# ArduinoInterface_v4.net
KiCad netlist of a schematic drawn in EAGLE
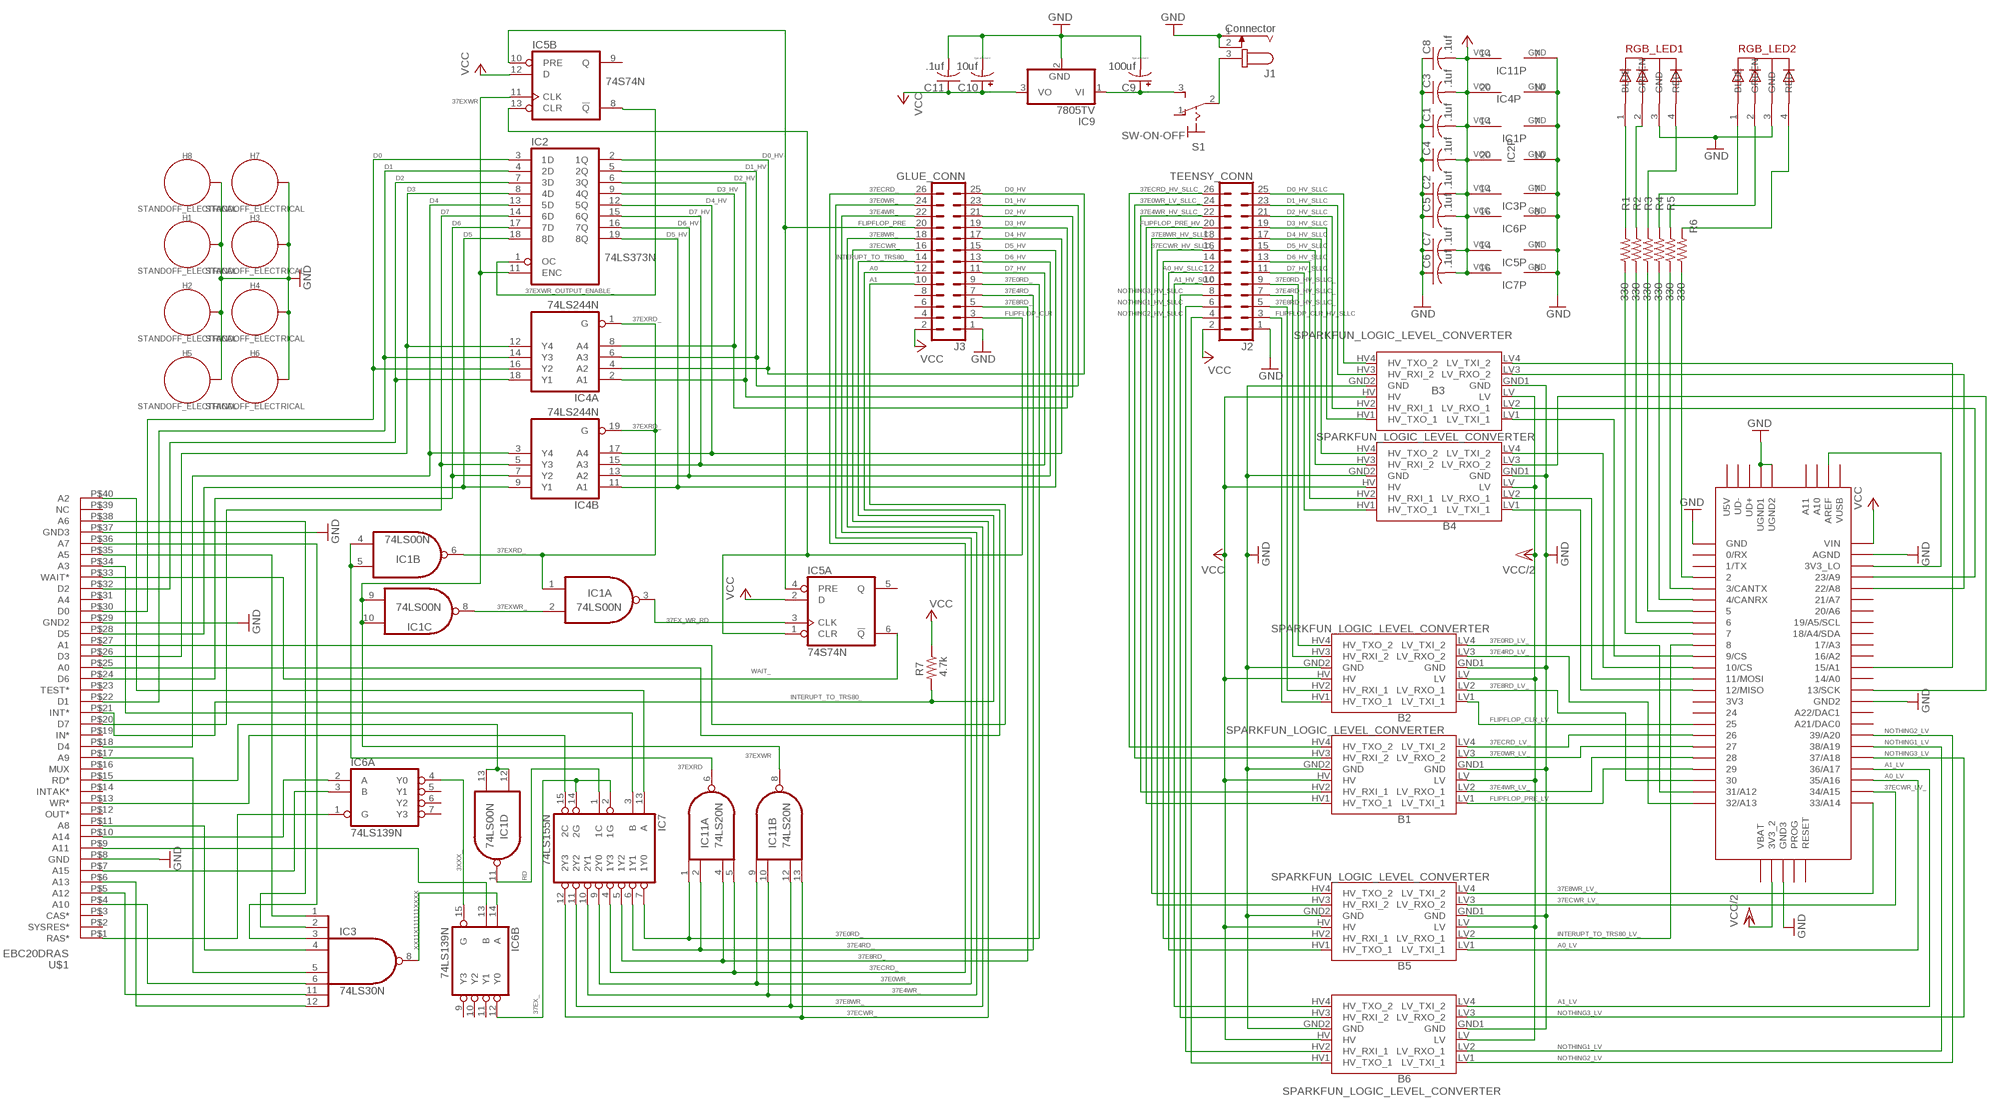
[diagram p0: schematic, sheet 1]

(export (version "E")
  (design (tool "Eeschema 10.0.6"))
  (components
    (comp (ref "B1")
      (value "SPARKFUN_LOGIC_LEVEL_CONVERTER")
      (footprint "eagle-import:SPARKFUN_LOGIC_LEVEL_CONVERTER")
      (libsource (lib "eagle-import") (part "SPARKFUN_LOGIC_LEVEL_CONVERTER"))
    )
    (comp (ref "B2")
      (value "SPARKFUN_LOGIC_LEVEL_CONVERTER")
      (footprint "eagle-import:SPARKFUN_LOGIC_LEVEL_CONVERTER")
      (libsource (lib "eagle-import") (part "SPARKFUN_LOGIC_LEVEL_CONVERTER"))
    )
    (comp (ref "B3")
      (value "SPARKFUN_LOGIC_LEVEL_CONVERTER")
      (footprint "eagle-import:SPARKFUN_LOGIC_LEVEL_CONVERTER")
      (libsource (lib "eagle-import") (part "SPARKFUN_LOGIC_LEVEL_CONVERTER"))
    )
    (comp (ref "B4")
      (value "SPARKFUN_LOGIC_LEVEL_CONVERTER")
      (footprint "eagle-import:SPARKFUN_LOGIC_LEVEL_CONVERTER")
      (libsource (lib "eagle-import") (part "SPARKFUN_LOGIC_LEVEL_CONVERTER"))
    )
    (comp (ref "B5")
      (value "SPARKFUN_LOGIC_LEVEL_CONVERTER")
      (footprint "eagle-import:SPARKFUN_LOGIC_LEVEL_CONVERTER")
      (libsource (lib "eagle-import") (part "SPARKFUN_LOGIC_LEVEL_CONVERTER"))
    )
    (comp (ref "B6")
      (value "SPARKFUN_LOGIC_LEVEL_CONVERTER")
      (footprint "eagle-import:SPARKFUN_LOGIC_LEVEL_CONVERTER")
      (libsource (lib "eagle-import") (part "SPARKFUN_LOGIC_LEVEL_CONVERTER"))
    )
    (comp (ref "C1")
      (value ".1uf")
      (footprint "eagle-import:C025-025X050")
      (libsource (lib "eagle-import") (part "C-US025-025X050"))
    )
    (comp (ref "C2")
      (value ".1uf")
      (footprint "eagle-import:C025-025X050")
      (libsource (lib "eagle-import") (part "C-US025-025X050"))
    )
    (comp (ref "C3")
      (value ".1uf")
      (footprint "eagle-import:C025-025X050")
      (libsource (lib "eagle-import") (part "C-US025-025X050"))
    )
    (comp (ref "C4")
      (value ".1uf")
      (footprint "eagle-import:C025-025X050")
      (libsource (lib "eagle-import") (part "C-US025-025X050"))
    )
    (comp (ref "C5")
      (value ".1uf")
      (footprint "eagle-import:C025-025X050")
      (libsource (lib "eagle-import") (part "C-US025-025X050"))
    )
    (comp (ref "C6")
      (value ".1uf")
      (footprint "eagle-import:C025-025X050")
      (libsource (lib "eagle-import") (part "C-US025-025X050"))
    )
    (comp (ref "C7")
      (value ".1uf")
      (footprint "eagle-import:C025-025X050")
      (libsource (lib "eagle-import") (part "C-US025-025X050"))
    )
    (comp (ref "C8")
      (value ".1uf")
      (footprint "eagle-import:C025-025X050")
      (libsource (lib "eagle-import") (part "C-US025-025X050"))
    )
    (comp (ref "C9")
      (value "100uf")
      (footprint "eagle-import:E5-6")
      (libsource (lib "eagle-import") (part "CPOL-USE5-6"))
    )
    (comp (ref "C10")
      (value "10uf")
      (footprint "eagle-import:E5-6")
      (libsource (lib "eagle-import") (part "CPOL-USE5-6"))
    )
    (comp (ref "C11")
      (value ".1uf")
      (footprint "eagle-import:C025-025X050")
      (libsource (lib "eagle-import") (part "C-US025-025X050"))
    )
    (comp (ref "H1")
      (value "STANDOFF_ELECTRICAL")
      (footprint "eagle-import:STANDOFF-ELECTRICAL")
      (libsource (lib "eagle-import") (part "STANDOFF_ELECTRICAL"))
    )
    (comp (ref "H2")
      (value "STANDOFF_ELECTRICAL")
      (footprint "eagle-import:STANDOFF-ELECTRICAL")
      (libsource (lib "eagle-import") (part "STANDOFF_ELECTRICAL"))
    )
    (comp (ref "H3")
      (value "STANDOFF_ELECTRICAL")
      (footprint "eagle-import:STANDOFF-ELECTRICAL")
      (libsource (lib "eagle-import") (part "STANDOFF_ELECTRICAL"))
    )
    (comp (ref "H4")
      (value "STANDOFF_ELECTRICAL")
      (footprint "eagle-import:STANDOFF-ELECTRICAL")
      (libsource (lib "eagle-import") (part "STANDOFF_ELECTRICAL"))
    )
    (comp (ref "H5")
      (value "STANDOFF_ELECTRICAL")
      (footprint "eagle-import:STANDOFF-ELECTRICAL")
      (libsource (lib "eagle-import") (part "STANDOFF_ELECTRICAL"))
    )
    (comp (ref "H6")
      (value "STANDOFF_ELECTRICAL")
      (footprint "eagle-import:STANDOFF-ELECTRICAL")
      (libsource (lib "eagle-import") (part "STANDOFF_ELECTRICAL"))
    )
    (comp (ref "H7")
      (value "STANDOFF_ELECTRICAL")
      (footprint "eagle-import:STANDOFF-ELECTRICAL")
      (libsource (lib "eagle-import") (part "STANDOFF_ELECTRICAL"))
    )
    (comp (ref "H8")
      (value "STANDOFF_ELECTRICAL")
      (footprint "eagle-import:STANDOFF-ELECTRICAL")
      (libsource (lib "eagle-import") (part "STANDOFF_ELECTRICAL"))
    )
    (comp (ref "IC1")
      (value "74LS00N")
      (footprint "eagle-import:DIL14")
      (libsource (lib "eagle-import") (part "7400NLS"))
    )
    (comp (ref "IC2")
      (value "74LS373N")
      (footprint "eagle-import:DIL20")
      (libsource (lib "eagle-import") (part "74373NLS"))
    )
    (comp (ref "IC3")
      (value "74LS30N")
      (footprint "eagle-import:DIL14")
      (libsource (lib "eagle-import") (part "7430NLS"))
    )
    (comp (ref "IC4")
      (value "74LS244N")
      (footprint "eagle-import:DIL20")
      (libsource (lib "eagle-import") (part "74244NLS"))
    )
    (comp (ref "IC5")
      (value "74S74N")
      (footprint "eagle-import:DIL14")
      (libsource (lib "eagle-import") (part "7474NS"))
    )
    (comp (ref "IC6")
      (value "74LS139N")
      (footprint "eagle-import:DIL16")
      (libsource (lib "eagle-import") (part "74139NLS"))
    )
    (comp (ref "IC7")
      (value "74LS155N")
      (footprint "eagle-import:DIL16")
      (libsource (lib "eagle-import") (part "74155NLS"))
    )
    (comp (ref "IC9")
      (value "7805TV")
      (footprint "eagle-import:TO220V")
      (libsource (lib "eagle-import") (part "78TV05"))
    )
    (comp (ref "IC11")
      (value "74LS20N")
      (footprint "eagle-import:DIL14")
      (libsource (lib "eagle-import") (part "7420NLS"))
    )
    (comp (ref "J1")
      (value "Connector")
      (footprint "eagle-import:SPC4077")
      (libsource (lib "eagle-import") (part "JACK-PLUG0"))
    )
    (comp (ref "J2")
      (value "TEENSY_CONN")
      (footprint "eagle-import:2X13")
      (libsource (lib "eagle-import") (part "CONN_13X22X13"))
    )
    (comp (ref "J3")
      (value "GLUE_CONN")
      (footprint "eagle-import:2X13")
      (libsource (lib "eagle-import") (part "CONN_13X22X13"))
    )
    (comp (ref "R1")
      (value "330")
      (footprint "eagle-import:0204V")
      (libsource (lib "eagle-import") (part "R-US_0204/2V"))
    )
    (comp (ref "R2")
      (value "330")
      (footprint "eagle-import:0204V")
      (libsource (lib "eagle-import") (part "R-US_0204/2V"))
    )
    (comp (ref "R3")
      (value "330")
      (footprint "eagle-import:0204V")
      (libsource (lib "eagle-import") (part "R-US_0204/2V"))
    )
    (comp (ref "R4")
      (value "330")
      (footprint "eagle-import:0204V")
      (libsource (lib "eagle-import") (part "R-US_0204/2V"))
    )
    (comp (ref "R5")
      (value "330")
      (footprint "eagle-import:0204V")
      (libsource (lib "eagle-import") (part "R-US_0204/2V"))
    )
    (comp (ref "R6")
      (value "330")
      (footprint "eagle-import:0204V")
      (libsource (lib "eagle-import") (part "R-US_0204/2V"))
    )
    (comp (ref "R7")
      (value "4.7k")
      (footprint "eagle-import:0204V")
      (libsource (lib "eagle-import") (part "R-US_0204/2V"))
    )
    (comp (ref "RGB_LED1")
      (value "5MMRGBLED")
      (footprint "eagle-import:LED5MMRGB")
      (libsource (lib "eagle-import") (part "5MMRGBLED"))
    )
    (comp (ref "RGB_LED2")
      (value "5MMRGBLED")
      (footprint "eagle-import:LED5MMRGB")
      (libsource (lib "eagle-import") (part "5MMRGBLED"))
    )
    (comp (ref "S1")
      (value "SW-ON-OFF")
      (footprint "eagle-import:M9040P")
      (libsource (lib "eagle-import") (part "M9040P"))
    )
    (comp (ref "U$1")
      (value "EBC20DRAS")
      (footprint "eagle-import:EBC20DRAS")
      (libsource (lib "eagle-import") (part "EBC20DRAS"))
    )
    (comp (ref "U$2")
      (value "TEENSY_3.5/3.6")
      (footprint "eagle-import:TEENSY_3.5_3.6")
      (libsource (lib "eagle-import") (part "TEENSY_3.5/3.6"))
    )
  )
  (nets
    (net (code "1") (name "/3XXX_") (class "Default")
      (node (ref "IC6") (pin "15") (pinfunction "G_15") (pintype "input"))
      (node (ref "IC6") (pin "4") (pinfunction "Y0_4") (pintype "output"))
    )
    (net (code "2") (name "/37E0RD_") (class "Default")
      (node (ref "IC11") (pin "1") (pinfunction "I0_1") (pintype "input"))
      (node (ref "IC7") (pin "7") (pinfunction "1Y0_7") (pintype "output"))
      (node (ref "J3") (pin "9") (pinfunction "9_9") (pintype "passive"))
    )
    (net (code "3") (name "/37E0RD_HV_SLLC_") (class "Default")
      (node (ref "B2") (pin "HV4") (pinfunction "HV_TXO_2_HV4") (pintype "bidirectional"))
      (node (ref "J2") (pin "9") (pinfunction "9_9") (pintype "passive"))
    )
    (net (code "4") (name "/37E0RD_LV_") (class "Default")
      (node (ref "B2") (pin "LV4") (pinfunction "LV_TXI_2_LV4") (pintype "bidirectional"))
      (node (ref "U$2") (pin "31/A12") (pinfunction "31/A12_31/A12") (pintype "bidirectional"))
    )
    (net (code "5") (name "/37E0WR_") (class "Default")
      (node (ref "IC11") (pin "9") (pinfunction "I0_9") (pintype "input"))
      (node (ref "IC7") (pin "9") (pinfunction "2Y0_9") (pintype "output"))
      (node (ref "J3") (pin "24") (pinfunction "24_24") (pintype "passive"))
    )
    (net (code "6") (name "/37E0WR_LV_") (class "Default")
      (node (ref "B1") (pin "LV3") (pinfunction "LV_RXO_2_LV3") (pintype "bidirectional"))
      (node (ref "U$2") (pin "27") (pinfunction "27_27") (pintype "bidirectional"))
    )
    (net (code "7") (name "/37E0WR_LV_SLLC_") (class "Default")
      (node (ref "B1") (pin "HV3") (pinfunction "HV_RXI_2_HV3") (pintype "bidirectional"))
      (node (ref "J2") (pin "24") (pinfunction "24_24") (pintype "passive"))
    )
    (net (code "8") (name "/37E4RD_") (class "Default")
      (node (ref "IC11") (pin "2") (pinfunction "I1_2") (pintype "input"))
      (node (ref "IC7") (pin "6") (pinfunction "1Y1_6") (pintype "output"))
      (node (ref "J3") (pin "7") (pinfunction "7_7") (pintype "passive"))
    )
    (net (code "9") (name "/37E4RD_HV_SLLC_") (class "Default")
      (node (ref "B2") (pin "HV3") (pinfunction "HV_RXI_2_HV3") (pintype "bidirectional"))
      (node (ref "J2") (pin "7") (pinfunction "7_7") (pintype "passive"))
    )
    (net (code "10") (name "/37E4RD_LV_") (class "Default")
      (node (ref "B2") (pin "LV3") (pinfunction "LV_RXO_2_LV3") (pintype "bidirectional"))
      (node (ref "U$2") (pin "32/A13") (pinfunction "32/A13_32/A13") (pintype "bidirectional"))
    )
    (net (code "11") (name "/37E4WR_") (class "Default")
      (node (ref "IC11") (pin "10") (pinfunction "I1_10") (pintype "input"))
      (node (ref "IC7") (pin "10") (pinfunction "2Y1_10") (pintype "output"))
      (node (ref "J3") (pin "22") (pinfunction "22_22") (pintype "passive"))
    )
    (net (code "12") (name "/37E4WR_HV_SLLC_") (class "Default")
      (node (ref "B1") (pin "HV2") (pinfunction "HV_RXI_1_HV2") (pintype "bidirectional"))
      (node (ref "J2") (pin "22") (pinfunction "22_22") (pintype "passive"))
    )
    (net (code "13") (name "/37E4WR_LV_") (class "Default")
      (node (ref "B1") (pin "LV2") (pinfunction "LV_RXO_1_LV2") (pintype "bidirectional"))
      (node (ref "U$2") (pin "28") (pinfunction "28_28") (pintype "bidirectional"))
    )
    (net (code "14") (name "/37E8RD_") (class "Default")
      (node (ref "IC11") (pin "4") (pinfunction "I2_4") (pintype "input"))
      (node (ref "IC7") (pin "5") (pinfunction "1Y2_5") (pintype "output"))
      (node (ref "J3") (pin "5") (pinfunction "5_5") (pintype "passive"))
    )
    (net (code "15") (name "/37E8RD_HV_SLLC_") (class "Default")
      (node (ref "B2") (pin "HV2") (pinfunction "HV_RXI_1_HV2") (pintype "bidirectional"))
      (node (ref "J2") (pin "5") (pinfunction "5_5") (pintype "passive"))
    )
    (net (code "16") (name "/37E8RD_LV_") (class "Default")
      (node (ref "B2") (pin "LV2") (pinfunction "LV_RXO_1_LV2") (pintype "bidirectional"))
      (node (ref "U$2") (pin "30") (pinfunction "30_30") (pintype "bidirectional"))
    )
    (net (code "17") (name "/37E8WR_") (class "Default")
      (node (ref "IC11") (pin "12") (pinfunction "I2_12") (pintype "input"))
      (node (ref "IC7") (pin "11") (pinfunction "2Y2_11") (pintype "output"))
      (node (ref "J3") (pin "18") (pinfunction "18_18") (pintype "passive"))
    )
    (net (code "18") (name "/37E8WR_HV_SLLC_") (class "Default")
      (node (ref "B5") (pin "HV4") (pinfunction "HV_TXO_2_HV4") (pintype "bidirectional"))
      (node (ref "J2") (pin "18") (pinfunction "18_18") (pintype "passive"))
    )
    (net (code "19") (name "/37E8WR_LV_") (class "Default")
      (node (ref "B5") (pin "LV4") (pinfunction "LV_TXI_2_LV4") (pintype "bidirectional"))
      (node (ref "U$2") (pin "33/A14") (pinfunction "33/A14_33/A14") (pintype "bidirectional"))
    )
    (net (code "20") (name "/37ECRD_") (class "Default")
      (node (ref "IC11") (pin "5") (pinfunction "I3_5") (pintype "input"))
      (node (ref "IC7") (pin "4") (pinfunction "1Y3_4") (pintype "output"))
      (node (ref "J3") (pin "26") (pinfunction "26_26") (pintype "passive"))
    )
    (net (code "21") (name "/37ECRD_HV_SLLC_") (class "Default")
      (node (ref "B1") (pin "HV4") (pinfunction "HV_TXO_2_HV4") (pintype "bidirectional"))
      (node (ref "J2") (pin "26") (pinfunction "26_26") (pintype "passive"))
    )
    (net (code "22") (name "/37ECRD_LV_") (class "Default")
      (node (ref "B1") (pin "LV4") (pinfunction "LV_TXI_2_LV4") (pintype "bidirectional"))
      (node (ref "U$2") (pin "26") (pinfunction "26_26") (pintype "bidirectional"))
    )
    (net (code "23") (name "/37ECWR_") (class "Default")
      (node (ref "IC11") (pin "13") (pinfunction "I3_13") (pintype "input"))
      (node (ref "IC7") (pin "12") (pinfunction "2Y3_12") (pintype "output"))
      (node (ref "J3") (pin "16") (pinfunction "16_16") (pintype "passive"))
    )
    (net (code "24") (name "/37ECWR_HV_SLLC_") (class "Default")
      (node (ref "B5") (pin "HV3") (pinfunction "HV_RXI_2_HV3") (pintype "bidirectional"))
      (node (ref "J2") (pin "16") (pinfunction "16_16") (pintype "passive"))
    )
    (net (code "25") (name "/37ECWR_LV_") (class "Default")
      (node (ref "B5") (pin "LV3") (pinfunction "LV_RXO_2_LV3") (pintype "bidirectional"))
      (node (ref "U$2") (pin "34/A15") (pinfunction "34/A15_34/A15") (pintype "bidirectional"))
    )
    (net (code "26") (name "/37EXRD") (class "Default")
      (node (ref "IC1") (pin "4") (pinfunction "I0_4") (pintype "input"))
      (node (ref "IC1") (pin "5") (pinfunction "I1_5") (pintype "input"))
      (node (ref "IC11") (pin "6") (pinfunction "O_6") (pintype "output"))
    )
    (net (code "27") (name "/37EXRD_") (class "Default")
      (node (ref "IC1") (pin "1") (pinfunction "I0_1") (pintype "input"))
      (node (ref "IC1") (pin "6") (pinfunction "O_6") (pintype "output"))
      (node (ref "IC4") (pin "1") (pinfunction "G_1") (pintype "input"))
      (node (ref "IC4") (pin "19") (pinfunction "G_19") (pintype "input"))
    )
    (net (code "28") (name "/37EXWR") (class "Default")
      (node (ref "IC1") (pin "10") (pinfunction "I1_10") (pintype "input"))
      (node (ref "IC1") (pin "9") (pinfunction "I0_9") (pintype "input"))
      (node (ref "IC11") (pin "8") (pinfunction "O_8") (pintype "output"))
      (node (ref "IC2") (pin "11") (pinfunction "ENC_11") (pintype "input"))
      (node (ref "IC5") (pin "11") (pinfunction "CLK_11") (pintype "input"))
    )
    (net (code "29") (name "/37EXWR_") (class "Default")
      (node (ref "IC1") (pin "2") (pinfunction "I1_2") (pintype "input"))
      (node (ref "IC1") (pin "8") (pinfunction "O_8") (pintype "output"))
    )
    (net (code "30") (name "/37EXWR_OUTPUT_ENABLE_") (class "Default")
      (node (ref "IC2") (pin "1") (pinfunction "OC_1") (pintype "input"))
      (node (ref "IC5") (pin "8") (pinfunction "~{Q}_8") (pintype "output"))
    )
    (net (code "31") (name "/37EX_") (class "Default")
      (node (ref "IC6") (pin "12") (pinfunction "Y0_12") (pintype "output"))
      (node (ref "IC7") (pin "14") (pinfunction "2G_14") (pintype "input"))
      (node (ref "IC7") (pin "2") (pinfunction "1G_2") (pintype "input"))
    )
    (net (code "32") (name "/37EX_WR_RD") (class "Default")
      (node (ref "IC1") (pin "3") (pinfunction "O_3") (pintype "output"))
      (node (ref "IC5") (pin "3") (pinfunction "CLK_3") (pintype "input"))
    )
    (net (code "33") (name "/A0") (class "Default")
      (node (ref "J3") (pin "12") (pinfunction "12_12") (pintype "passive"))
      (node (ref "U$1") (pin "P$25") (pinfunction "A0_P$25") (pintype "bidirectional"))
    )
    (net (code "34") (name "/A0_HV_SLLC") (class "Default")
      (node (ref "B5") (pin "HV1") (pinfunction "HV_TXO_1_HV1") (pintype "bidirectional"))
      (node (ref "J2") (pin "12") (pinfunction "12_12") (pintype "passive"))
    )
    (net (code "35") (name "/A0_LV") (class "Default")
      (node (ref "B5") (pin "LV1") (pinfunction "LV_TXI_1_LV1") (pintype "bidirectional"))
      (node (ref "U$2") (pin "35/A16") (pinfunction "35/A16_35/A16") (pintype "bidirectional"))
    )
    (net (code "36") (name "/A1") (class "Default")
      (node (ref "J3") (pin "10") (pinfunction "10_10") (pintype "passive"))
      (node (ref "U$1") (pin "P$27") (pinfunction "A1_P$27") (pintype "bidirectional"))
    )
    (net (code "37") (name "/A1_HV_SLLC") (class "Default")
      (node (ref "B6") (pin "HV4") (pinfunction "HV_TXO_2_HV4") (pintype "bidirectional"))
      (node (ref "J2") (pin "10") (pinfunction "10_10") (pintype "passive"))
    )
    (net (code "38") (name "/A1_LV") (class "Default")
      (node (ref "B6") (pin "LV4") (pinfunction "LV_TXI_2_LV4") (pintype "bidirectional"))
      (node (ref "U$2") (pin "36/A17") (pinfunction "36/A17_36/A17") (pintype "bidirectional"))
    )
    (net (code "39") (name "/D0") (class "Default")
      (node (ref "IC2") (pin "3") (pinfunction "1D_3") (pintype "input"))
      (node (ref "IC4") (pin "16") (pinfunction "Y2_16") (pintype "tri_state"))
      (node (ref "U$1") (pin "P$30") (pinfunction "D0_P$30") (pintype "bidirectional"))
    )
    (net (code "40") (name "/D0_HV") (class "Default")
      (node (ref "IC2") (pin "2") (pinfunction "1Q_2") (pintype "tri_state"))
      (node (ref "IC4") (pin "4") (pinfunction "A2_4") (pintype "input"))
      (node (ref "J3") (pin "25") (pinfunction "25_25") (pintype "passive"))
    )
    (net (code "41") (name "/D0_HV_SLLC") (class "Default")
      (node (ref "B3") (pin "HV4") (pinfunction "HV_TXO_2_HV4") (pintype "bidirectional"))
      (node (ref "J2") (pin "25") (pinfunction "25_25") (pintype "passive"))
    )
    (net (code "42") (name "/D1") (class "Default")
      (node (ref "IC2") (pin "4") (pinfunction "2D_4") (pintype "input"))
      (node (ref "IC4") (pin "14") (pinfunction "Y3_14") (pintype "tri_state"))
      (node (ref "U$1") (pin "P$22") (pinfunction "D1_P$22") (pintype "bidirectional"))
    )
    (net (code "43") (name "/D1_HV") (class "Default")
      (node (ref "IC2") (pin "5") (pinfunction "2Q_5") (pintype "tri_state"))
      (node (ref "IC4") (pin "6") (pinfunction "A3_6") (pintype "input"))
      (node (ref "J3") (pin "23") (pinfunction "23_23") (pintype "passive"))
    )
    (net (code "44") (name "/D1_HV_SLLC") (class "Default")
      (node (ref "B3") (pin "HV3") (pinfunction "HV_RXI_2_HV3") (pintype "bidirectional"))
      (node (ref "J2") (pin "23") (pinfunction "23_23") (pintype "passive"))
    )
    (net (code "45") (name "/D2") (class "Default")
      (node (ref "IC2") (pin "7") (pinfunction "3D_7") (pintype "input"))
      (node (ref "IC4") (pin "18") (pinfunction "Y1_18") (pintype "tri_state"))
      (node (ref "U$1") (pin "P$32") (pinfunction "D2_P$32") (pintype "bidirectional"))
    )
    (net (code "46") (name "/D2_HV") (class "Default")
      (node (ref "IC2") (pin "6") (pinfunction "3Q_6") (pintype "tri_state"))
      (node (ref "IC4") (pin "2") (pinfunction "A1_2") (pintype "input"))
      (node (ref "J3") (pin "21") (pinfunction "21_21") (pintype "passive"))
    )
    (net (code "47") (name "/D2_HV_SLLC") (class "Default")
      (node (ref "B3") (pin "HV2") (pinfunction "HV_RXI_1_HV2") (pintype "bidirectional"))
      (node (ref "J2") (pin "21") (pinfunction "21_21") (pintype "passive"))
    )
    (net (code "48") (name "/D3") (class "Default")
      (node (ref "IC2") (pin "8") (pinfunction "4D_8") (pintype "input"))
      (node (ref "IC4") (pin "12") (pinfunction "Y4_12") (pintype "tri_state"))
      (node (ref "U$1") (pin "P$26") (pinfunction "D3_P$26") (pintype "bidirectional"))
    )
    (net (code "49") (name "/D3_HV") (class "Default")
      (node (ref "IC2") (pin "9") (pinfunction "4Q_9") (pintype "tri_state"))
      (node (ref "IC4") (pin "8") (pinfunction "A4_8") (pintype "input"))
      (node (ref "J3") (pin "19") (pinfunction "19_19") (pintype "passive"))
    )
    (net (code "50") (name "/D3_HV_SLLC") (class "Default")
      (node (ref "B3") (pin "HV1") (pinfunction "HV_TXO_1_HV1") (pintype "bidirectional"))
      (node (ref "J2") (pin "19") (pinfunction "19_19") (pintype "passive"))
    )
    (net (code "51") (name "/D4") (class "Default")
      (node (ref "IC2") (pin "13") (pinfunction "5D_13") (pintype "input"))
      (node (ref "IC4") (pin "3") (pinfunction "Y4_3") (pintype "tri_state"))
      (node (ref "U$1") (pin "P$18") (pinfunction "D4_P$18") (pintype "bidirectional"))
    )
    (net (code "52") (name "/D4_HV") (class "Default")
      (node (ref "IC2") (pin "12") (pinfunction "5Q_12") (pintype "tri_state"))
      (node (ref "IC4") (pin "17") (pinfunction "A4_17") (pintype "input"))
      (node (ref "J3") (pin "17") (pinfunction "17_17") (pintype "passive"))
    )
    (net (code "53") (name "/D4_HV_SLLC") (class "Default")
      (node (ref "B4") (pin "HV4") (pinfunction "HV_TXO_2_HV4") (pintype "bidirectional"))
      (node (ref "J2") (pin "17") (pinfunction "17_17") (pintype "passive"))
    )
    (net (code "54") (name "/D5") (class "Default")
      (node (ref "IC2") (pin "18") (pinfunction "8D_18") (pintype "input"))
      (node (ref "IC4") (pin "9") (pinfunction "Y1_9") (pintype "tri_state"))
      (node (ref "U$1") (pin "P$28") (pinfunction "D5_P$28") (pintype "bidirectional"))
    )
    (net (code "55") (name "/D5_HV") (class "Default")
      (node (ref "IC2") (pin "19") (pinfunction "8Q_19") (pintype "tri_state"))
      (node (ref "IC4") (pin "11") (pinfunction "A1_11") (pintype "input"))
      (node (ref "J3") (pin "15") (pinfunction "15_15") (pintype "passive"))
    )
    (net (code "56") (name "/D5_HV_SLLC") (class "Default")
      (node (ref "B4") (pin "HV3") (pinfunction "HV_RXI_2_HV3") (pintype "bidirectional"))
      (node (ref "J2") (pin "15") (pinfunction "15_15") (pintype "passive"))
    )
    (net (code "57") (name "/D6") (class "Default")
      (node (ref "IC2") (pin "17") (pinfunction "7D_17") (pintype "input"))
      (node (ref "IC4") (pin "7") (pinfunction "Y2_7") (pintype "tri_state"))
      (node (ref "U$1") (pin "P$24") (pinfunction "D6_P$24") (pintype "bidirectional"))
    )
    (net (code "58") (name "/D6_HV") (class "Default")
      (node (ref "IC2") (pin "16") (pinfunction "7Q_16") (pintype "tri_state"))
      (node (ref "IC4") (pin "13") (pinfunction "A2_13") (pintype "input"))
      (node (ref "J3") (pin "13") (pinfunction "13_13") (pintype "passive"))
    )
    (net (code "59") (name "/D6_HV_SLLC") (class "Default")
      (node (ref "B4") (pin "HV2") (pinfunction "HV_RXI_1_HV2") (pintype "bidirectional"))
      (node (ref "J2") (pin "13") (pinfunction "13_13") (pintype "passive"))
    )
    (net (code "60") (name "/D7") (class "Default")
      (node (ref "IC2") (pin "14") (pinfunction "6D_14") (pintype "input"))
      (node (ref "IC4") (pin "5") (pinfunction "Y3_5") (pintype "tri_state"))
      (node (ref "U$1") (pin "P$20") (pinfunction "D7_P$20") (pintype "bidirectional"))
    )
    (net (code "61") (name "/D7_HV") (class "Default")
      (node (ref "IC2") (pin "15") (pinfunction "6Q_15") (pintype "tri_state"))
      (node (ref "IC4") (pin "15") (pinfunction "A3_15") (pintype "input"))
      (node (ref "J3") (pin "11") (pinfunction "11_11") (pintype "passive"))
    )
    (net (code "62") (name "/D7_HV_SLLC") (class "Default")
      (node (ref "B4") (pin "HV1") (pinfunction "HV_TXO_1_HV1") (pintype "bidirectional"))
      (node (ref "J2") (pin "11") (pinfunction "11_11") (pintype "passive"))
    )
    (net (code "63") (name "/FLIPFLOP_CLR") (class "Default")
      (node (ref "IC5") (pin "1") (pinfunction "CLR_1") (pintype "input"))
      (node (ref "IC5") (pin "13") (pinfunction "CLR_13") (pintype "input"))
      (node (ref "J3") (pin "3") (pinfunction "3_3") (pintype "passive"))
    )
    (net (code "64") (name "/FLIPFLOP_CLR_HV_SLLC") (class "Default")
      (node (ref "B2") (pin "HV1") (pinfunction "HV_TXO_1_HV1") (pintype "bidirectional"))
      (node (ref "J2") (pin "3") (pinfunction "3_3") (pintype "passive"))
    )
    (net (code "65") (name "/FLIPFLOP_CLR_LV") (class "Default")
      (node (ref "B2") (pin "LV1") (pinfunction "LV_TXI_1_LV1") (pintype "bidirectional"))
      (node (ref "U$2") (pin "25") (pinfunction "25_25") (pintype "bidirectional"))
    )
    (net (code "66") (name "/FLIPFLOP_PRE") (class "Default")
      (node (ref "IC5") (pin "10") (pinfunction "PRE_10") (pintype "input"))
      (node (ref "IC5") (pin "4") (pinfunction "PRE_4") (pintype "input"))
      (node (ref "J3") (pin "20") (pinfunction "20_20") (pintype "passive"))
    )
    (net (code "67") (name "/FLIPFLOP_PRE_HV") (class "Default")
      (node (ref "B1") (pin "HV1") (pinfunction "HV_TXO_1_HV1") (pintype "bidirectional"))
      (node (ref "J2") (pin "20") (pinfunction "20_20") (pintype "passive"))
    )
    (net (code "68") (name "/FLIPFLOP_PRE_LV") (class "Default")
      (node (ref "B1") (pin "LV1") (pinfunction "LV_TXI_1_LV1") (pintype "bidirectional"))
      (node (ref "U$2") (pin "29") (pinfunction "29_29") (pintype "bidirectional"))
    )
    (net (code "69") (name "/INTERUPT_TO_TRS80_") (class "Default")
      (node (ref "J3") (pin "14") (pinfunction "14_14") (pintype "passive"))
      (node (ref "R7") (pin "2") (pinfunction "2_2") (pintype "passive"))
      (node (ref "U$1") (pin "P$21") (pinfunction "INT*_P$21") (pintype "bidirectional"))
    )
    (net (code "70") (name "/INTERUPT_TO_TRS80_LV_") (class "Default")
      (node (ref "B5") (pin "LV2") (pinfunction "LV_RXO_1_LV2") (pintype "bidirectional"))
      (node (ref "U$2") (pin "8") (pinfunction "8_8") (pintype "bidirectional"))
    )
    (net (code "71") (name "/NOTHING1_HV_SLLC") (class "Default")
      (node (ref "B6") (pin "HV2") (pinfunction "HV_RXI_1_HV2") (pintype "bidirectional"))
      (node (ref "J2") (pin "6") (pinfunction "6_6") (pintype "passive"))
    )
    (net (code "72") (name "/NOTHING1_LV") (class "Default")
      (node (ref "B6") (pin "LV2") (pinfunction "LV_RXO_1_LV2") (pintype "bidirectional"))
      (node (ref "U$2") (pin "38/A19") (pinfunction "38/A19_38/A19") (pintype "bidirectional"))
    )
    (net (code "73") (name "/NOTHING2_HV_SLLC") (class "Default")
      (node (ref "B6") (pin "HV1") (pinfunction "HV_TXO_1_HV1") (pintype "bidirectional"))
      (node (ref "J2") (pin "4") (pinfunction "4_4") (pintype "passive"))
    )
    (net (code "74") (name "/NOTHING2_LV") (class "Default")
      (node (ref "B6") (pin "LV1") (pinfunction "LV_TXI_1_LV1") (pintype "bidirectional"))
      (node (ref "U$2") (pin "39/A20") (pinfunction "39/A20_39/A20") (pintype "bidirectional"))
    )
    (net (code "75") (name "/NOTHING3_HV_SLLC") (class "Default")
      (node (ref "B6") (pin "HV3") (pinfunction "HV_RXI_2_HV3") (pintype "bidirectional"))
      (node (ref "J2") (pin "8") (pinfunction "8_8") (pintype "passive"))
    )
    (net (code "76") (name "/NOTHING3_LV") (class "Default")
      (node (ref "B6") (pin "LV3") (pinfunction "LV_RXO_2_LV3") (pintype "bidirectional"))
      (node (ref "U$2") (pin "37/A18") (pinfunction "37/A18_37/A18") (pintype "bidirectional"))
    )
    (net (code "77") (name "/RD") (class "Default")
      (node (ref "IC1") (pin "11") (pinfunction "O_11") (pintype "output"))
      (node (ref "IC7") (pin "1") (pinfunction "1C_1") (pintype "input"))
    )
    (net (code "78") (name "/WAIT_") (class "Default")
      (node (ref "IC5") (pin "6") (pinfunction "~{Q}_6") (pintype "output"))
      (node (ref "U$1") (pin "P$33") (pinfunction "WAIT*_P$33") (pintype "bidirectional"))
    )
    (net (code "79") (name "/XX11X111111XXXX") (class "Default")
      (node (ref "IC3") (pin "8") (pinfunction "O_8") (pintype "output"))
      (node (ref "IC6") (pin "14") (pinfunction "A_14") (pintype "input"))
    )
    (net (code "80") (name "GND") (class "Default")
      (node (ref "B1") (pin "GND1") (pinfunction "GND_GND1") (pintype "power_in"))
      (node (ref "B1") (pin "GND2") (pinfunction "GND_GND2") (pintype "power_in"))
      (node (ref "B2") (pin "GND1") (pinfunction "GND_GND1") (pintype "power_in"))
      (node (ref "B2") (pin "GND2") (pinfunction "GND_GND2") (pintype "power_in"))
      (node (ref "B3") (pin "GND1") (pinfunction "GND_GND1") (pintype "power_in"))
      (node (ref "B3") (pin "GND2") (pinfunction "GND_GND2") (pintype "power_in"))
      (node (ref "B4") (pin "GND1") (pinfunction "GND_GND1") (pintype "power_in"))
      (node (ref "B4") (pin "GND2") (pinfunction "GND_GND2") (pintype "power_in"))
      (node (ref "B5") (pin "GND1") (pinfunction "GND_GND1") (pintype "power_in"))
      (node (ref "B5") (pin "GND2") (pinfunction "GND_GND2") (pintype "power_in"))
      (node (ref "B6") (pin "GND1") (pinfunction "GND_GND1") (pintype "power_in"))
      (node (ref "B6") (pin "GND2") (pinfunction "GND_GND2") (pintype "power_in"))
      (node (ref "C1") (pin "1") (pinfunction "1_1") (pintype "passive"))
      (node (ref "C10") (pin "-") (pinfunction "-_-") (pintype "passive"))
      (node (ref "C11") (pin "2") (pinfunction "2_2") (pintype "passive"))
      (node (ref "C2") (pin "1") (pinfunction "1_1") (pintype "passive"))
      (node (ref "C3") (pin "1") (pinfunction "1_1") (pintype "passive"))
      (node (ref "C4") (pin "1") (pinfunction "1_1") (pintype "passive"))
      (node (ref "C5") (pin "1") (pinfunction "1_1") (pintype "passive"))
      (node (ref "C6") (pin "1") (pinfunction "1_1") (pintype "passive"))
      (node (ref "C7") (pin "1") (pinfunction "1_1") (pintype "passive"))
      (node (ref "C8") (pin "1") (pinfunction "1_1") (pintype "passive"))
      (node (ref "C9") (pin "-") (pinfunction "-_-") (pintype "passive"))
      (node (ref "H1") (pin "P1") (pinfunction "P$1_P1") (pintype "bidirectional"))
      (node (ref "H2") (pin "P1") (pinfunction "P$1_P1") (pintype "bidirectional"))
      (node (ref "H3") (pin "P1") (pinfunction "P$1_P1") (pintype "bidirectional"))
      (node (ref "H4") (pin "P1") (pinfunction "P$1_P1") (pintype "bidirectional"))
      (node (ref "H5") (pin "P1") (pinfunction "P$1_P1") (pintype "bidirectional"))
      (node (ref "H6") (pin "P1") (pinfunction "P$1_P1") (pintype "bidirectional"))
      (node (ref "H7") (pin "P1") (pinfunction "P$1_P1") (pintype "bidirectional"))
      (node (ref "H8") (pin "P1") (pinfunction "P$1_P1") (pintype "bidirectional"))
      (node (ref "IC1") (pin "7") (pinfunction "GND_7") (pintype "power_in"))
      (node (ref "IC11") (pin "7") (pinfunction "GND_7") (pintype "power_in"))
      (node (ref "IC2") (pin "10") (pinfunction "GND_10") (pintype "power_in"))
      (node (ref "IC3") (pin "7") (pinfunction "GND_7") (pintype "power_in"))
      (node (ref "IC4") (pin "10") (pinfunction "GND_10") (pintype "power_in"))
      (node (ref "IC5") (pin "7") (pinfunction "GND_7") (pintype "power_in"))
      (node (ref "IC6") (pin "8") (pinfunction "GND_8") (pintype "power_in"))
      (node (ref "IC7") (pin "8") (pinfunction "GND_8") (pintype "power_in"))
      (node (ref "IC9") (pin "2") (pinfunction "GND_2") (pintype "passive"))
      (node (ref "J1") (pin "1") (pinfunction "1_1") (pintype "passive"))
      (node (ref "J1") (pin "2") (pinfunction "2_2") (pintype "passive"))
      (node (ref "J2") (pin "1") (pinfunction "1_1") (pintype "passive"))
      (node (ref "J3") (pin "1") (pinfunction "1_1") (pintype "passive"))
      (node (ref "RGB_LED1") (pin "3") (pinfunction "GND_3") (pintype "bidirectional"))
      (node (ref "RGB_LED2") (pin "3") (pinfunction "GND_3") (pintype "bidirectional"))
      (node (ref "U$1") (pin "P$29") (pinfunction "GND2_P$29") (pintype "bidirectional"))
      (node (ref "U$1") (pin "P$37") (pinfunction "GND3_P$37") (pintype "bidirectional"))
      (node (ref "U$1") (pin "P$8") (pinfunction "GND_P$8") (pintype "bidirectional"))
      (node (ref "U$2") (pin "AGND") (pinfunction "AGND_AGND") (pintype "bidirectional"))
      (node (ref "U$2") (pin "GND") (pinfunction "GND_GND") (pintype "bidirectional"))
      (node (ref "U$2") (pin "GND2") (pinfunction "GND2_GND2") (pintype "bidirectional"))
      (node (ref "U$2") (pin "GND3") (pinfunction "GND3_GND3") (pintype "bidirectional"))
      (node (ref "U$2") (pin "UGND1") (pinfunction "UGND1_UGND1") (pintype "bidirectional"))
      (node (ref "U$2") (pin "UGND2") (pinfunction "UGND2_UGND2") (pintype "bidirectional"))
    )
    (net (code "81") (name "Net-(B3-LV_RXO_1)") (class "Default")
      (node (ref "B3") (pin "LV2") (pinfunction "LV_RXO_1_LV2") (pintype "bidirectional"))
      (node (ref "U$2") (pin "23/A9") (pinfunction "23/A9_23/A9") (pintype "bidirectional"))
    )
    (net (code "82") (name "Net-(B3-LV_RXO_2)") (class "Default")
      (node (ref "B3") (pin "LV3") (pinfunction "LV_RXO_2_LV3") (pintype "bidirectional"))
      (node (ref "U$2") (pin "22/A8") (pinfunction "22/A8_22/A8") (pintype "bidirectional"))
    )
    (net (code "83") (name "Net-(B3-LV_TXI_1)") (class "Default")
      (node (ref "B3") (pin "LV1") (pinfunction "LV_TXI_1_LV1") (pintype "bidirectional"))
      (node (ref "U$2") (pin "9/CS") (pinfunction "9/CS_9/CS") (pintype "bidirectional"))
    )
    (net (code "84") (name "Net-(B3-LV_TXI_2)") (class "Default")
      (node (ref "B3") (pin "LV4") (pinfunction "LV_TXI_2_LV4") (pintype "bidirectional"))
      (node (ref "U$2") (pin "15/A1") (pinfunction "15/A1_15/A1") (pintype "bidirectional"))
    )
    (net (code "85") (name "Net-(B4-LV_RXO_1)") (class "Default")
      (node (ref "B4") (pin "LV2") (pinfunction "LV_RXO_1_LV2") (pintype "bidirectional"))
      (node (ref "U$2") (pin "11/MOSI") (pinfunction "11/MOSI_11/MOSI") (pintype "bidirectional"))
    )
    (net (code "86") (name "Net-(B4-LV_RXO_2)") (class "Default")
      (node (ref "B4") (pin "LV3") (pinfunction "LV_RXO_2_LV3") (pintype "bidirectional"))
      (node (ref "U$2") (pin "13/SCK") (pinfunction "13/SCK_13/SCK") (pintype "bidirectional"))
    )
    (net (code "87") (name "Net-(B4-LV_TXI_1)") (class "Default")
      (node (ref "B4") (pin "LV1") (pinfunction "LV_TXI_1_LV1") (pintype "bidirectional"))
      (node (ref "U$2") (pin "12/MISO") (pinfunction "12/MISO_12/MISO") (pintype "bidirectional"))
    )
    (net (code "88") (name "Net-(B4-LV_TXI_2)") (class "Default")
      (node (ref "B4") (pin "LV4") (pinfunction "LV_TXI_2_LV4") (pintype "bidirectional"))
      (node (ref "U$2") (pin "10/CS") (pinfunction "10/CS_10/CS") (pintype "bidirectional"))
    )
    (net (code "89") (name "Net-(B5-HV_RXI_1)") (class "Default")
      (node (ref "B5") (pin "HV2") (pinfunction "HV_RXI_1_HV2") (pintype "bidirectional"))
      (node (ref "J2") (pin "14") (pinfunction "14_14") (pintype "passive"))
    )
    (net (code "90") (name "Net-(IC1D-I0)") (class "Default")
      (node (ref "IC1") (pin "12") (pinfunction "I0_12") (pintype "input"))
      (node (ref "IC1") (pin "13") (pinfunction "I1_13") (pintype "input"))
      (node (ref "U$1") (pin "P$15") (pinfunction "RD*_P$15") (pintype "bidirectional"))
    )
    (net (code "91") (name "Net-(IC3A-I0)") (class "Default")
      (node (ref "IC3") (pin "1") (pinfunction "I0_1") (pintype "input"))
      (node (ref "U$1") (pin "P$35") (pinfunction "A5_P$35") (pintype "bidirectional"))
    )
    (net (code "92") (name "Net-(IC3A-I1)") (class "Default")
      (node (ref "IC3") (pin "2") (pinfunction "I1_2") (pintype "input"))
      (node (ref "U$1") (pin "P$38") (pinfunction "A6_P$38") (pintype "bidirectional"))
    )
    (net (code "93") (name "Net-(IC3A-I2)") (class "Default")
      (node (ref "IC3") (pin "3") (pinfunction "I2_3") (pintype "input"))
      (node (ref "U$1") (pin "P$36") (pinfunction "A7_P$36") (pintype "bidirectional"))
    )
    (net (code "94") (name "Net-(IC3A-I3)") (class "Default")
      (node (ref "IC3") (pin "4") (pinfunction "I3_4") (pintype "input"))
      (node (ref "U$1") (pin "P$11") (pinfunction "A8_P$11") (pintype "bidirectional"))
    )
    (net (code "95") (name "Net-(IC3A-I4)") (class "Default")
      (node (ref "IC3") (pin "5") (pinfunction "I4_5") (pintype "input"))
      (node (ref "U$1") (pin "P$17") (pinfunction "A9_P$17") (pintype "bidirectional"))
    )
    (net (code "96") (name "Net-(IC3A-I5)") (class "Default")
      (node (ref "IC3") (pin "6") (pinfunction "I5_6") (pintype "input"))
      (node (ref "U$1") (pin "P$4") (pinfunction "A10_P$4") (pintype "bidirectional"))
    )
    (net (code "97") (name "Net-(IC3A-I6)") (class "Default")
      (node (ref "IC3") (pin "11") (pinfunction "I6_11") (pintype "input"))
      (node (ref "U$1") (pin "P$5") (pinfunction "A12_P$5") (pintype "bidirectional"))
    )
    (net (code "98") (name "Net-(IC3A-I7)") (class "Default")
      (node (ref "IC3") (pin "12") (pinfunction "I7_12") (pintype "input"))
      (node (ref "U$1") (pin "P$6") (pinfunction "A13_P$6") (pintype "bidirectional"))
    )
    (net (code "99") (name "Net-(IC6A-A)") (class "Default")
      (node (ref "IC6") (pin "2") (pinfunction "A_2") (pintype "input"))
      (node (ref "U$1") (pin "P$10") (pinfunction "A14_P$10") (pintype "bidirectional"))
    )
    (net (code "100") (name "Net-(IC6A-B)") (class "Default")
      (node (ref "IC6") (pin "3") (pinfunction "B_3") (pintype "input"))
      (node (ref "U$1") (pin "P$7") (pinfunction "A15_P$7") (pintype "bidirectional"))
    )
    (net (code "101") (name "Net-(IC6A-G)") (class "Default")
      (node (ref "IC6") (pin "1") (pinfunction "G_1") (pintype "input"))
      (node (ref "U$1") (pin "P$1") (pinfunction "RAS*_P$1") (pintype "bidirectional"))
    )
    (net (code "102") (name "Net-(IC6B-B)") (class "Default")
      (node (ref "IC6") (pin "13") (pinfunction "B_13") (pintype "input"))
      (node (ref "U$1") (pin "P$9") (pinfunction "A11_P$9") (pintype "bidirectional"))
    )
    (net (code "103") (name "Net-(IC7A-2C)") (class "Default")
      (node (ref "IC7") (pin "15") (pinfunction "2C_15") (pintype "input"))
      (node (ref "U$1") (pin "P$13") (pinfunction "WR*_P$13") (pintype "bidirectional"))
    )
    (net (code "104") (name "Net-(IC7A-A)") (class "Default")
      (node (ref "IC7") (pin "13") (pinfunction "A_13") (pintype "input"))
      (node (ref "U$1") (pin "P$40") (pinfunction "A2_P$40") (pintype "bidirectional"))
    )
    (net (code "105") (name "Net-(IC7A-B)") (class "Default")
      (node (ref "IC7") (pin "3") (pinfunction "B_3") (pintype "input"))
      (node (ref "U$1") (pin "P$34") (pinfunction "A3_P$34") (pintype "bidirectional"))
    )
    (net (code "106") (name "Net-(IC9-VI)") (class "Default")
      (node (ref "C9") (pin "+") (pinfunction "+_+") (pintype "passive"))
      (node (ref "IC9") (pin "1") (pinfunction "VI_1") (pintype "input"))
      (node (ref "S1") (pin "3") (pinfunction "S_3") (pintype "passive"))
    )
    (net (code "107") (name "Net-(R1-Pad1)") (class "Default")
      (node (ref "R1") (pin "1") (pinfunction "1_1") (pintype "passive"))
      (node (ref "U$2") (pin "7") (pinfunction "7_7") (pintype "bidirectional"))
    )
    (net (code "108") (name "Net-(R2-Pad1)") (class "Default")
      (node (ref "R2") (pin "1") (pinfunction "1_1") (pintype "passive"))
      (node (ref "U$2") (pin "6") (pinfunction "6_6") (pintype "bidirectional"))
    )
    (net (code "109") (name "Net-(R3-Pad1)") (class "Default")
      (node (ref "R3") (pin "1") (pinfunction "1_1") (pintype "passive"))
      (node (ref "U$2") (pin "5") (pinfunction "5_5") (pintype "bidirectional"))
    )
    (net (code "110") (name "Net-(R4-Pad1)") (class "Default")
      (node (ref "R4") (pin "1") (pinfunction "1_1") (pintype "passive"))
      (node (ref "U$2") (pin "4/CANRX") (pinfunction "4/CANRX_4/CANRX") (pintype "bidirectional"))
    )
    (net (code "111") (name "Net-(R5-Pad1)") (class "Default")
      (node (ref "R5") (pin "1") (pinfunction "1_1") (pintype "passive"))
      (node (ref "U$2") (pin "3/CANTX") (pinfunction "3/CANTX_3/CANTX") (pintype "bidirectional"))
    )
    (net (code "112") (name "Net-(R6-Pad1)") (class "Default")
      (node (ref "R6") (pin "1") (pinfunction "1_1") (pintype "passive"))
      (node (ref "U$2") (pin "2") (pinfunction "2_2") (pintype "bidirectional"))
    )
    (net (code "113") (name "Net-(RGB_LED1-BLUE)") (class "Default")
      (node (ref "R1") (pin "2") (pinfunction "2_2") (pintype "passive"))
      (node (ref "RGB_LED1") (pin "1") (pinfunction "BLUE_1") (pintype "bidirectional"))
    )
    (net (code "114") (name "Net-(RGB_LED1-GREEN)") (class "Default")
      (node (ref "R2") (pin "2") (pinfunction "2_2") (pintype "passive"))
      (node (ref "RGB_LED1") (pin "2") (pinfunction "GREEN_2") (pintype "bidirectional"))
    )
    (net (code "115") (name "Net-(RGB_LED1-RED)") (class "Default")
      (node (ref "R3") (pin "2") (pinfunction "2_2") (pintype "passive"))
      (node (ref "RGB_LED1") (pin "4") (pinfunction "RED_4") (pintype "bidirectional"))
    )
    (net (code "116") (name "Net-(RGB_LED2-BLUE)") (class "Default")
      (node (ref "R4") (pin "2") (pinfunction "2_2") (pintype "passive"))
      (node (ref "RGB_LED2") (pin "1") (pinfunction "BLUE_1") (pintype "bidirectional"))
    )
    (net (code "117") (name "Net-(RGB_LED2-GREEN)") (class "Default")
      (node (ref "R5") (pin "2") (pinfunction "2_2") (pintype "passive"))
      (node (ref "RGB_LED2") (pin "2") (pinfunction "GREEN_2") (pintype "bidirectional"))
    )
    (net (code "118") (name "Net-(RGB_LED2-RED)") (class "Default")
      (node (ref "R6") (pin "2") (pinfunction "2_2") (pintype "passive"))
      (node (ref "RGB_LED2") (pin "4") (pinfunction "RED_4") (pintype "bidirectional"))
    )
    (net (code "119") (name "Net-(S1-P)") (class "Default")
      (node (ref "J1") (pin "3") (pinfunction "3_3") (pintype "passive"))
      (node (ref "S1") (pin "2") (pinfunction "P_2") (pintype "passive"))
    )
    (net (code "120") (name "Net-(U$2-Pad3V3_LO)") (class "Default")
      (node (ref "U$2") (pin "3V3_LO") (pinfunction "3V3_LO_3V3_LO") (pintype "bidirectional"))
      (node (ref "U$2") (pin "AREF") (pinfunction "AREF_AREF") (pintype "bidirectional"))
    )
    (net (code "121") (name "VCC") (class "Default")
      (node (ref "B1") (pin "HV") (pinfunction "HV_HV") (pintype "power_in"))
      (node (ref "B2") (pin "HV") (pinfunction "HV_HV") (pintype "power_in"))
      (node (ref "B3") (pin "HV") (pinfunction "HV_HV") (pintype "power_in"))
      (node (ref "B4") (pin "HV") (pinfunction "HV_HV") (pintype "power_in"))
      (node (ref "B5") (pin "HV") (pinfunction "HV_HV") (pintype "power_in"))
      (node (ref "B6") (pin "HV") (pinfunction "HV_HV") (pintype "power_in"))
      (node (ref "C1") (pin "2") (pinfunction "2_2") (pintype "passive"))
      (node (ref "C10") (pin "+") (pinfunction "+_+") (pintype "passive"))
      (node (ref "C11") (pin "1") (pinfunction "1_1") (pintype "passive"))
      (node (ref "C2") (pin "2") (pinfunction "2_2") (pintype "passive"))
      (node (ref "C3") (pin "2") (pinfunction "2_2") (pintype "passive"))
      (node (ref "C4") (pin "2") (pinfunction "2_2") (pintype "passive"))
      (node (ref "C5") (pin "2") (pinfunction "2_2") (pintype "passive"))
      (node (ref "C6") (pin "2") (pinfunction "2_2") (pintype "passive"))
      (node (ref "C7") (pin "2") (pinfunction "2_2") (pintype "passive"))
      (node (ref "C8") (pin "2") (pinfunction "2_2") (pintype "passive"))
      (node (ref "IC1") (pin "14") (pinfunction "VCC_14") (pintype "power_in"))
      (node (ref "IC11") (pin "14") (pinfunction "VCC_14") (pintype "power_in"))
      (node (ref "IC2") (pin "20") (pinfunction "VCC_20") (pintype "power_in"))
      (node (ref "IC3") (pin "14") (pinfunction "VCC_14") (pintype "power_in"))
      (node (ref "IC4") (pin "20") (pinfunction "VCC_20") (pintype "power_in"))
      (node (ref "IC5") (pin "12") (pinfunction "D_12") (pintype "input"))
      (node (ref "IC5") (pin "14") (pinfunction "VCC_14") (pintype "power_in"))
      (node (ref "IC5") (pin "2") (pinfunction "D_2") (pintype "input"))
      (node (ref "IC6") (pin "16") (pinfunction "VCC_16") (pintype "power_in"))
      (node (ref "IC7") (pin "16") (pinfunction "VCC_16") (pintype "power_in"))
      (node (ref "IC9") (pin "3") (pinfunction "VO_3") (pintype "passive"))
      (node (ref "J2") (pin "2") (pinfunction "2_2") (pintype "passive"))
      (node (ref "J3") (pin "2") (pinfunction "2_2") (pintype "passive"))
      (node (ref "R7") (pin "1") (pinfunction "1_1") (pintype "passive"))
      (node (ref "U$2") (pin "VIN") (pinfunction "VIN_VIN") (pintype "bidirectional"))
    )
    (net (code "122") (name "VCC{slash}2") (class "Default")
      (node (ref "B1") (pin "LV") (pinfunction "LV_LV") (pintype "power_in"))
      (node (ref "B2") (pin "LV") (pinfunction "LV_LV") (pintype "power_in"))
      (node (ref "B3") (pin "LV") (pinfunction "LV_LV") (pintype "power_in"))
      (node (ref "B4") (pin "LV") (pinfunction "LV_LV") (pintype "power_in"))
      (node (ref "B5") (pin "LV") (pinfunction "LV_LV") (pintype "power_in"))
      (node (ref "B6") (pin "LV") (pinfunction "LV_LV") (pintype "power_in"))
      (node (ref "U$2") (pin "3V3_2") (pinfunction "3V3_2_3V3_2") (pintype "bidirectional"))
    )
    (net (code "123") (name "unconnected-(IC5A-Q-Pad5)") (class "Default")
      (node (ref "IC5") (pin "5") (pinfunction "Q_5") (pintype "output"))
    )
    (net (code "124") (name "unconnected-(IC5B-Q-Pad9)") (class "Default")
      (node (ref "IC5") (pin "9") (pinfunction "Q_9") (pintype "output"))
    )
    (net (code "125") (name "unconnected-(IC6A-Y1-Pad5)") (class "Default")
      (node (ref "IC6") (pin "5") (pinfunction "Y1_5") (pintype "output"))
    )
    (net (code "126") (name "unconnected-(IC6A-Y2-Pad6)") (class "Default")
      (node (ref "IC6") (pin "6") (pinfunction "Y2_6") (pintype "output"))
    )
    (net (code "127") (name "unconnected-(IC6A-Y3-Pad7)") (class "Default")
      (node (ref "IC6") (pin "7") (pinfunction "Y3_7") (pintype "output"))
    )
    (net (code "128") (name "unconnected-(IC6B-Y1-Pad11)") (class "Default")
      (node (ref "IC6") (pin "11") (pinfunction "Y1_11") (pintype "output"))
    )
    (net (code "129") (name "unconnected-(IC6B-Y2-Pad10)") (class "Default")
      (node (ref "IC6") (pin "10") (pinfunction "Y2_10") (pintype "output"))
    )
    (net (code "130") (name "unconnected-(IC6B-Y3-Pad9)") (class "Default")
      (node (ref "IC6") (pin "9") (pinfunction "Y3_9") (pintype "output"))
    )
    (net (code "131") (name "unconnected-(J3-Pad4)") (class "Default")
      (node (ref "J3") (pin "4") (pinfunction "4_4") (pintype "passive"))
    )
    (net (code "132") (name "unconnected-(J3-Pad6)") (class "Default")
      (node (ref "J3") (pin "6") (pinfunction "6_6") (pintype "passive"))
    )
    (net (code "133") (name "unconnected-(J3-Pad8)") (class "Default")
      (node (ref "J3") (pin "8") (pinfunction "8_8") (pintype "passive"))
    )
    (net (code "134") (name "unconnected-(S1-O-Pad1)") (class "Default")
      (node (ref "S1") (pin "1") (pinfunction "O_1") (pintype "passive"))
    )
    (net (code "135") (name "unconnected-(U$1-A4-PadP$31)") (class "Default")
      (node (ref "U$1") (pin "P$31") (pinfunction "A4_P$31") (pintype "bidirectional"))
    )
    (net (code "136") (name "unconnected-(U$1-CAS*-PadP$3)") (class "Default")
      (node (ref "U$1") (pin "P$3") (pinfunction "CAS*_P$3") (pintype "bidirectional"))
    )
    (net (code "137") (name "unconnected-(U$1-IN*-PadP$19)") (class "Default")
      (node (ref "U$1") (pin "P$19") (pinfunction "IN*_P$19") (pintype "bidirectional"))
    )
    (net (code "138") (name "unconnected-(U$1-INTAK*-PadP$14)") (class "Default")
      (node (ref "U$1") (pin "P$14") (pinfunction "INTAK*_P$14") (pintype "bidirectional"))
    )
    (net (code "139") (name "unconnected-(U$1-MUX-PadP$16)") (class "Default")
      (node (ref "U$1") (pin "P$16") (pinfunction "MUX_P$16") (pintype "bidirectional"))
    )
    (net (code "140") (name "unconnected-(U$1-NC-PadP$39)") (class "Default")
      (node (ref "U$1") (pin "P$39") (pinfunction "NC_P$39") (pintype "bidirectional"))
    )
    (net (code "141") (name "unconnected-(U$1-OUT*-PadP$12)") (class "Default")
      (node (ref "U$1") (pin "P$12") (pinfunction "OUT*_P$12") (pintype "bidirectional"))
    )
    (net (code "142") (name "unconnected-(U$1-SYSRES*-PadP$2)") (class "Default")
      (node (ref "U$1") (pin "P$2") (pinfunction "SYSRES*_P$2") (pintype "bidirectional"))
    )
    (net (code "143") (name "unconnected-(U$1-TEST*-PadP$23)") (class "Default")
      (node (ref "U$1") (pin "P$23") (pinfunction "TEST*_P$23") (pintype "bidirectional"))
    )
    (net (code "144") (name "unconnected-(U$2-A21{slash}DAC0-Pad21{slash}DAC0)") (class "Default")
      (node (ref "U$2") (pin "21/DAC0") (pinfunction "A21/DAC0_21/DAC0") (pintype "bidirectional"))
    )
    (net (code "145") (name "unconnected-(U$2-Pad0{slash}RX)") (class "Default")
      (node (ref "U$2") (pin "0/RX") (pinfunction "0/RX_0/RX") (pintype "bidirectional"))
    )
    (net (code "146") (name "unconnected-(U$2-Pad1{slash}TX)") (class "Default")
      (node (ref "U$2") (pin "1/TX") (pinfunction "1/TX_1/TX") (pintype "bidirectional"))
    )
    (net (code "147") (name "unconnected-(U$2-Pad3V3)") (class "Default")
      (node (ref "U$2") (pin "3V3") (pinfunction "3V3_3V3") (pintype "bidirectional"))
    )
    (net (code "148") (name "unconnected-(U$2-Pad14{slash}A0)") (class "Default")
      (node (ref "U$2") (pin "14/A0") (pinfunction "14/A0_14/A0") (pintype "bidirectional"))
    )
    (net (code "149") (name "unconnected-(U$2-Pad16{slash}A2)") (class "Default")
      (node (ref "U$2") (pin "16/A2") (pinfunction "16/A2_16/A2") (pintype "bidirectional"))
    )
    (net (code "150") (name "unconnected-(U$2-Pad17{slash}A3)") (class "Default")
      (node (ref "U$2") (pin "17/A3") (pinfunction "17/A3_17/A3") (pintype "bidirectional"))
    )
    (net (code "151") (name "unconnected-(U$2-Pad18{slash}A4{slash}SDA)") (class "Default")
      (node (ref "U$2") (pin "18/A4/SDA") (pinfunction "18/A4/SDA_18/A4/SDA") (pintype "bidirectional"))
    )
    (net (code "152") (name "unconnected-(U$2-Pad19{slash}A5{slash}SCL)") (class "Default")
      (node (ref "U$2") (pin "19/A5/SCL") (pinfunction "19/A5/SCL_19/A5/SCL") (pintype "bidirectional"))
    )
    (net (code "153") (name "unconnected-(U$2-Pad20{slash}A6)") (class "Default")
      (node (ref "U$2") (pin "20/A6") (pinfunction "20/A6_20/A6") (pintype "bidirectional"))
    )
    (net (code "154") (name "unconnected-(U$2-Pad21{slash}A7)") (class "Default")
      (node (ref "U$2") (pin "21/A7") (pinfunction "21/A7_21/A7") (pintype "bidirectional"))
    )
    (net (code "155") (name "unconnected-(U$2-Pad24)") (class "Default")
      (node (ref "U$2") (pin "24") (pinfunction "24_24") (pintype "bidirectional"))
    )
    (net (code "156") (name "unconnected-(U$2-PadA10)") (class "Default")
      (node (ref "U$2") (pin "A10") (pinfunction "A10_A10") (pintype "bidirectional"))
    )
    (net (code "157") (name "unconnected-(U$2-PadA11)") (class "Default")
      (node (ref "U$2") (pin "A11") (pinfunction "A11_A11") (pintype "bidirectional"))
    )
    (net (code "158") (name "unconnected-(U$2-PadA22{slash}DAC1)") (class "Default")
      (node (ref "U$2") (pin "A22/DAC1") (pinfunction "A22/DAC1_A22/DAC1") (pintype "bidirectional"))
    )
    (net (code "159") (name "unconnected-(U$2-PadPROG)") (class "Default")
      (node (ref "U$2") (pin "PROG") (pinfunction "PROG_PROG") (pintype "bidirectional"))
    )
    (net (code "160") (name "unconnected-(U$2-PadRESET)") (class "Default")
      (node (ref "U$2") (pin "RESET") (pinfunction "RESET_RESET") (pintype "bidirectional"))
    )
    (net (code "161") (name "unconnected-(U$2-PadU5V)") (class "Default")
      (node (ref "U$2") (pin "U5V") (pinfunction "U5V_U5V") (pintype "bidirectional"))
    )
    (net (code "162") (name "unconnected-(U$2-PadUD+)") (class "Default")
      (node (ref "U$2") (pin "UD+") (pinfunction "UD+_UD+") (pintype "bidirectional"))
    )
    (net (code "163") (name "unconnected-(U$2-PadUD-)") (class "Default")
      (node (ref "U$2") (pin "UD-") (pinfunction "UD-_UD-") (pintype "bidirectional"))
    )
    (net (code "164") (name "unconnected-(U$2-PadVBAT)") (class "Default")
      (node (ref "U$2") (pin "VBAT") (pinfunction "VBAT_VBAT") (pintype "bidirectional"))
    )
    (net (code "165") (name "unconnected-(U$2-PadVUSB)") (class "Default")
      (node (ref "U$2") (pin "VUSB") (pinfunction "VUSB_VUSB") (pintype "bidirectional"))
    )
  )
)
